# ECU_JUMPER.net
KiCad netlist of a schematic drawn in EAGLE
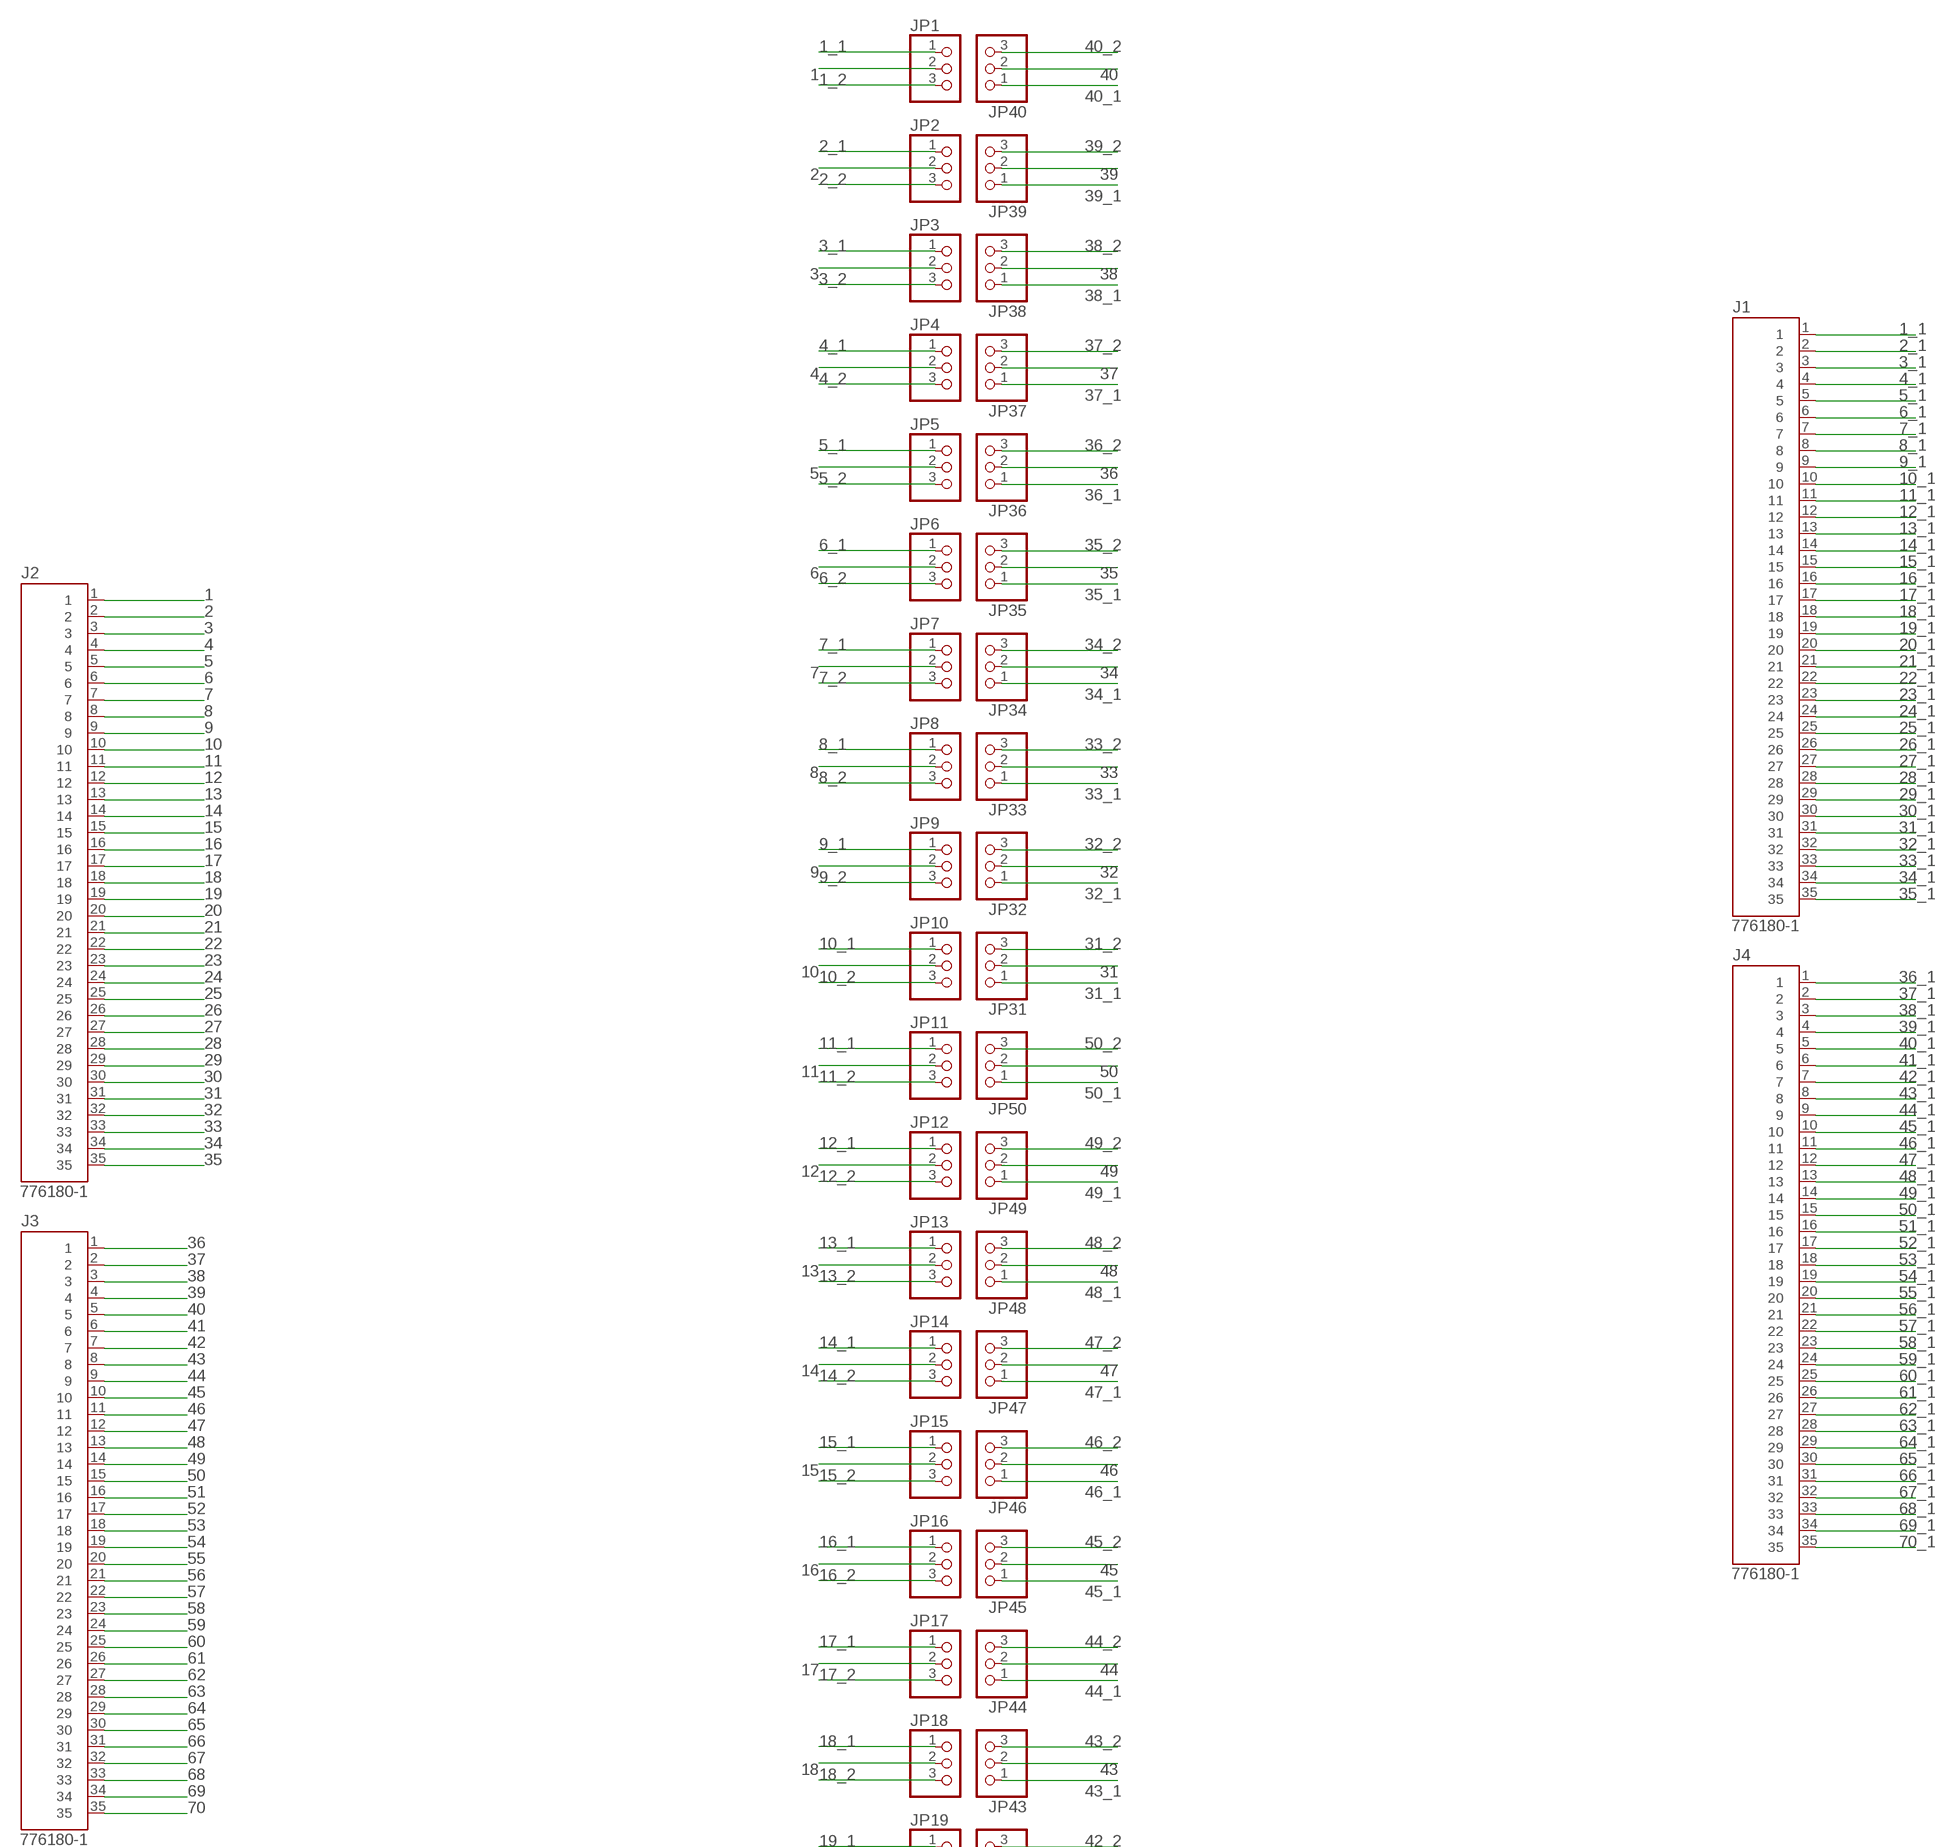
[diagram p0: schematic, sheet 1, part 1 of 2]
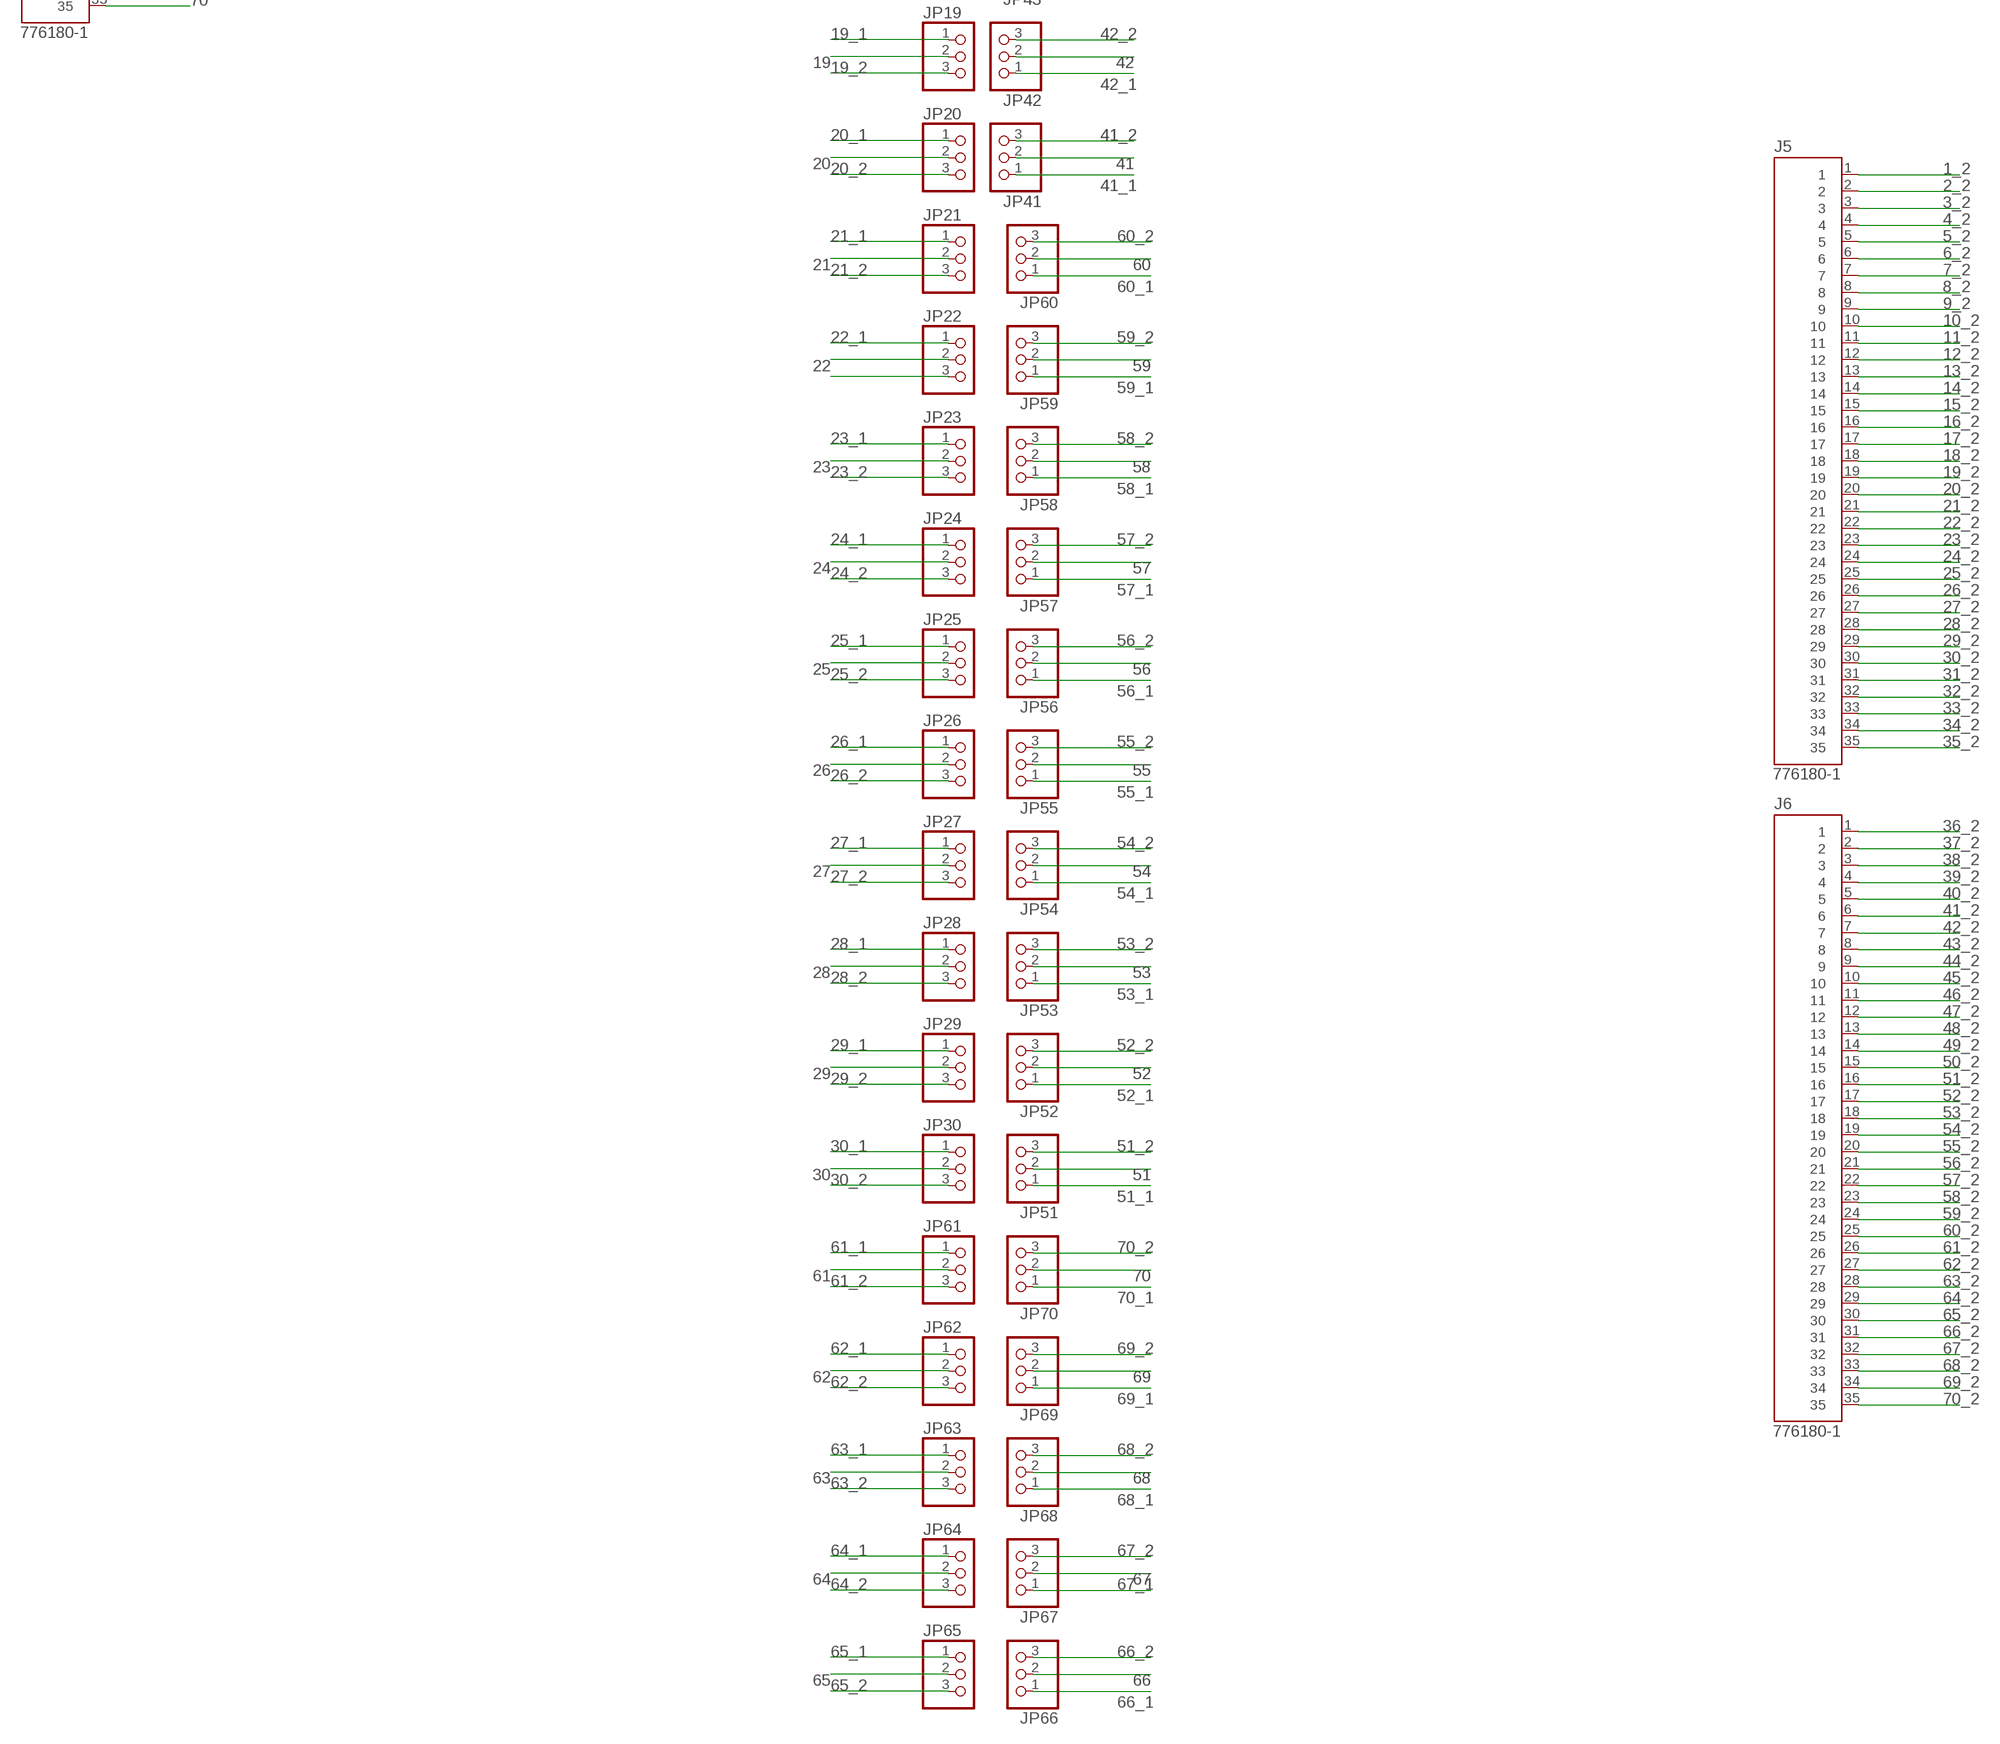
[diagram p1: schematic, sheet 1, part 2 of 2]

(export (version "E")
  (design (tool "Eeschema 10.0.6"))
  (components
    (comp (ref "J1")
      (value "776180-1")
      (footprint "eagle-import:TE_776180-1")
      (fields (field (name "MANUFACTURER") "TE CONNECTIVITY"))
      (libsource (lib "eagle-import") (part "776180-1"))
    )
    (comp (ref "J2")
      (value "776180-1")
      (footprint "eagle-import:TE_776180-1")
      (fields (field (name "MANUFACTURER") "TE CONNECTIVITY"))
      (libsource (lib "eagle-import") (part "776180-1"))
    )
    (comp (ref "J3")
      (value "776180-1")
      (footprint "eagle-import:TE_776180-1")
      (fields (field (name "MANUFACTURER") "TE CONNECTIVITY"))
      (libsource (lib "eagle-import") (part "776180-1"))
    )
    (comp (ref "J4")
      (value "776180-1")
      (footprint "eagle-import:TE_776180-1")
      (fields (field (name "MANUFACTURER") "TE CONNECTIVITY"))
      (libsource (lib "eagle-import") (part "776180-1"))
    )
    (comp (ref "J5")
      (value "776180-1")
      (footprint "eagle-import:TE_776180-1")
      (fields (field (name "MANUFACTURER") "TE CONNECTIVITY"))
      (libsource (lib "eagle-import") (part "776180-1"))
    )
    (comp (ref "J6")
      (value "776180-1")
      (footprint "eagle-import:TE_776180-1")
      (fields (field (name "MANUFACTURER") "TE CONNECTIVITY"))
      (libsource (lib "eagle-import") (part "776180-1"))
    )
    (comp (ref "JP1")
      (value "PINHD-1X3")
      (footprint "eagle-import:1X03")
      (libsource (lib "eagle-import") (part "PINHD-1X3"))
    )
    (comp (ref "JP2")
      (value "PINHD-1X3")
      (footprint "eagle-import:1X03")
      (libsource (lib "eagle-import") (part "PINHD-1X3"))
    )
    (comp (ref "JP3")
      (value "PINHD-1X3")
      (footprint "eagle-import:1X03")
      (libsource (lib "eagle-import") (part "PINHD-1X3"))
    )
    (comp (ref "JP4")
      (value "PINHD-1X3")
      (footprint "eagle-import:1X03")
      (libsource (lib "eagle-import") (part "PINHD-1X3"))
    )
    (comp (ref "JP5")
      (value "PINHD-1X3")
      (footprint "eagle-import:1X03")
      (libsource (lib "eagle-import") (part "PINHD-1X3"))
    )
    (comp (ref "JP6")
      (value "PINHD-1X3")
      (footprint "eagle-import:1X03")
      (libsource (lib "eagle-import") (part "PINHD-1X3"))
    )
    (comp (ref "JP7")
      (value "PINHD-1X3")
      (footprint "eagle-import:1X03")
      (libsource (lib "eagle-import") (part "PINHD-1X3"))
    )
    (comp (ref "JP8")
      (value "PINHD-1X3")
      (footprint "eagle-import:1X03")
      (libsource (lib "eagle-import") (part "PINHD-1X3"))
    )
    (comp (ref "JP9")
      (value "PINHD-1X3")
      (footprint "eagle-import:1X03")
      (libsource (lib "eagle-import") (part "PINHD-1X3"))
    )
    (comp (ref "JP10")
      (value "PINHD-1X3")
      (footprint "eagle-import:1X03")
      (libsource (lib "eagle-import") (part "PINHD-1X3"))
    )
    (comp (ref "JP11")
      (value "PINHD-1X3")
      (footprint "eagle-import:1X03")
      (libsource (lib "eagle-import") (part "PINHD-1X3"))
    )
    (comp (ref "JP12")
      (value "PINHD-1X3")
      (footprint "eagle-import:1X03")
      (libsource (lib "eagle-import") (part "PINHD-1X3"))
    )
    (comp (ref "JP13")
      (value "PINHD-1X3")
      (footprint "eagle-import:1X03")
      (libsource (lib "eagle-import") (part "PINHD-1X3"))
    )
    (comp (ref "JP14")
      (value "PINHD-1X3")
      (footprint "eagle-import:1X03")
      (libsource (lib "eagle-import") (part "PINHD-1X3"))
    )
    (comp (ref "JP15")
      (value "PINHD-1X3")
      (footprint "eagle-import:1X03")
      (libsource (lib "eagle-import") (part "PINHD-1X3"))
    )
    (comp (ref "JP16")
      (value "PINHD-1X3")
      (footprint "eagle-import:1X03")
      (libsource (lib "eagle-import") (part "PINHD-1X3"))
    )
    (comp (ref "JP17")
      (value "PINHD-1X3")
      (footprint "eagle-import:1X03")
      (libsource (lib "eagle-import") (part "PINHD-1X3"))
    )
    (comp (ref "JP18")
      (value "PINHD-1X3")
      (footprint "eagle-import:1X03")
      (libsource (lib "eagle-import") (part "PINHD-1X3"))
    )
    (comp (ref "JP19")
      (value "PINHD-1X3")
      (footprint "eagle-import:1X03")
      (libsource (lib "eagle-import") (part "PINHD-1X3"))
    )
    (comp (ref "JP20")
      (value "PINHD-1X3")
      (footprint "eagle-import:1X03")
      (libsource (lib "eagle-import") (part "PINHD-1X3"))
    )
    (comp (ref "JP21")
      (value "PINHD-1X3")
      (footprint "eagle-import:1X03")
      (libsource (lib "eagle-import") (part "PINHD-1X3"))
    )
    (comp (ref "JP22")
      (value "PINHD-1X3")
      (footprint "eagle-import:1X03")
      (libsource (lib "eagle-import") (part "PINHD-1X3"))
    )
    (comp (ref "JP23")
      (value "PINHD-1X3")
      (footprint "eagle-import:1X03")
      (libsource (lib "eagle-import") (part "PINHD-1X3"))
    )
    (comp (ref "JP24")
      (value "PINHD-1X3")
      (footprint "eagle-import:1X03")
      (libsource (lib "eagle-import") (part "PINHD-1X3"))
    )
    (comp (ref "JP25")
      (value "PINHD-1X3")
      (footprint "eagle-import:1X03")
      (libsource (lib "eagle-import") (part "PINHD-1X3"))
    )
    (comp (ref "JP26")
      (value "PINHD-1X3")
      (footprint "eagle-import:1X03")
      (libsource (lib "eagle-import") (part "PINHD-1X3"))
    )
    (comp (ref "JP27")
      (value "PINHD-1X3")
      (footprint "eagle-import:1X03")
      (libsource (lib "eagle-import") (part "PINHD-1X3"))
    )
    (comp (ref "JP28")
      (value "PINHD-1X3")
      (footprint "eagle-import:1X03")
      (libsource (lib "eagle-import") (part "PINHD-1X3"))
    )
    (comp (ref "JP29")
      (value "PINHD-1X3")
      (footprint "eagle-import:1X03")
      (libsource (lib "eagle-import") (part "PINHD-1X3"))
    )
    (comp (ref "JP30")
      (value "PINHD-1X3")
      (footprint "eagle-import:1X03")
      (libsource (lib "eagle-import") (part "PINHD-1X3"))
    )
    (comp (ref "JP31")
      (value "PINHD-1X3")
      (footprint "eagle-import:1X03")
      (libsource (lib "eagle-import") (part "PINHD-1X3"))
    )
    (comp (ref "JP32")
      (value "PINHD-1X3")
      (footprint "eagle-import:1X03")
      (libsource (lib "eagle-import") (part "PINHD-1X3"))
    )
    (comp (ref "JP33")
      (value "PINHD-1X3")
      (footprint "eagle-import:1X03")
      (libsource (lib "eagle-import") (part "PINHD-1X3"))
    )
    (comp (ref "JP34")
      (value "PINHD-1X3")
      (footprint "eagle-import:1X03")
      (libsource (lib "eagle-import") (part "PINHD-1X3"))
    )
    (comp (ref "JP35")
      (value "PINHD-1X3")
      (footprint "eagle-import:1X03")
      (libsource (lib "eagle-import") (part "PINHD-1X3"))
    )
    (comp (ref "JP36")
      (value "PINHD-1X3")
      (footprint "eagle-import:1X03")
      (libsource (lib "eagle-import") (part "PINHD-1X3"))
    )
    (comp (ref "JP37")
      (value "PINHD-1X3")
      (footprint "eagle-import:1X03")
      (libsource (lib "eagle-import") (part "PINHD-1X3"))
    )
    (comp (ref "JP38")
      (value "PINHD-1X3")
      (footprint "eagle-import:1X03")
      (libsource (lib "eagle-import") (part "PINHD-1X3"))
    )
    (comp (ref "JP39")
      (value "PINHD-1X3")
      (footprint "eagle-import:1X03")
      (libsource (lib "eagle-import") (part "PINHD-1X3"))
    )
    (comp (ref "JP40")
      (value "PINHD-1X3")
      (footprint "eagle-import:1X03")
      (libsource (lib "eagle-import") (part "PINHD-1X3"))
    )
    (comp (ref "JP41")
      (value "PINHD-1X3")
      (footprint "eagle-import:1X03")
      (libsource (lib "eagle-import") (part "PINHD-1X3"))
    )
    (comp (ref "JP42")
      (value "PINHD-1X3")
      (footprint "eagle-import:1X03")
      (libsource (lib "eagle-import") (part "PINHD-1X3"))
    )
    (comp (ref "JP43")
      (value "PINHD-1X3")
      (footprint "eagle-import:1X03")
      (libsource (lib "eagle-import") (part "PINHD-1X3"))
    )
    (comp (ref "JP44")
      (value "PINHD-1X3")
      (footprint "eagle-import:1X03")
      (libsource (lib "eagle-import") (part "PINHD-1X3"))
    )
    (comp (ref "JP45")
      (value "PINHD-1X3")
      (footprint "eagle-import:1X03")
      (libsource (lib "eagle-import") (part "PINHD-1X3"))
    )
    (comp (ref "JP46")
      (value "PINHD-1X3")
      (footprint "eagle-import:1X03")
      (libsource (lib "eagle-import") (part "PINHD-1X3"))
    )
    (comp (ref "JP47")
      (value "PINHD-1X3")
      (footprint "eagle-import:1X03")
      (libsource (lib "eagle-import") (part "PINHD-1X3"))
    )
    (comp (ref "JP48")
      (value "PINHD-1X3")
      (footprint "eagle-import:1X03")
      (libsource (lib "eagle-import") (part "PINHD-1X3"))
    )
    (comp (ref "JP49")
      (value "PINHD-1X3")
      (footprint "eagle-import:1X03")
      (libsource (lib "eagle-import") (part "PINHD-1X3"))
    )
    (comp (ref "JP50")
      (value "PINHD-1X3")
      (footprint "eagle-import:1X03")
      (libsource (lib "eagle-import") (part "PINHD-1X3"))
    )
    (comp (ref "JP51")
      (value "PINHD-1X3")
      (footprint "eagle-import:1X03")
      (libsource (lib "eagle-import") (part "PINHD-1X3"))
    )
    (comp (ref "JP52")
      (value "PINHD-1X3")
      (footprint "eagle-import:1X03")
      (libsource (lib "eagle-import") (part "PINHD-1X3"))
    )
    (comp (ref "JP53")
      (value "PINHD-1X3")
      (footprint "eagle-import:1X03")
      (libsource (lib "eagle-import") (part "PINHD-1X3"))
    )
    (comp (ref "JP54")
      (value "PINHD-1X3")
      (footprint "eagle-import:1X03")
      (libsource (lib "eagle-import") (part "PINHD-1X3"))
    )
    (comp (ref "JP55")
      (value "PINHD-1X3")
      (footprint "eagle-import:1X03")
      (libsource (lib "eagle-import") (part "PINHD-1X3"))
    )
    (comp (ref "JP56")
      (value "PINHD-1X3")
      (footprint "eagle-import:1X03")
      (libsource (lib "eagle-import") (part "PINHD-1X3"))
    )
    (comp (ref "JP57")
      (value "PINHD-1X3")
      (footprint "eagle-import:1X03")
      (libsource (lib "eagle-import") (part "PINHD-1X3"))
    )
    (comp (ref "JP58")
      (value "PINHD-1X3")
      (footprint "eagle-import:1X03")
      (libsource (lib "eagle-import") (part "PINHD-1X3"))
    )
    (comp (ref "JP59")
      (value "PINHD-1X3")
      (footprint "eagle-import:1X03")
      (libsource (lib "eagle-import") (part "PINHD-1X3"))
    )
    (comp (ref "JP60")
      (value "PINHD-1X3")
      (footprint "eagle-import:1X03")
      (libsource (lib "eagle-import") (part "PINHD-1X3"))
    )
    (comp (ref "JP61")
      (value "PINHD-1X3")
      (footprint "eagle-import:1X03")
      (libsource (lib "eagle-import") (part "PINHD-1X3"))
    )
    (comp (ref "JP62")
      (value "PINHD-1X3")
      (footprint "eagle-import:1X03")
      (libsource (lib "eagle-import") (part "PINHD-1X3"))
    )
    (comp (ref "JP63")
      (value "PINHD-1X3")
      (footprint "eagle-import:1X03")
      (libsource (lib "eagle-import") (part "PINHD-1X3"))
    )
    (comp (ref "JP64")
      (value "PINHD-1X3")
      (footprint "eagle-import:1X03")
      (libsource (lib "eagle-import") (part "PINHD-1X3"))
    )
    (comp (ref "JP65")
      (value "PINHD-1X3")
      (footprint "eagle-import:1X03")
      (libsource (lib "eagle-import") (part "PINHD-1X3"))
    )
    (comp (ref "JP66")
      (value "PINHD-1X3")
      (footprint "eagle-import:1X03")
      (libsource (lib "eagle-import") (part "PINHD-1X3"))
    )
    (comp (ref "JP67")
      (value "PINHD-1X3")
      (footprint "eagle-import:1X03")
      (libsource (lib "eagle-import") (part "PINHD-1X3"))
    )
    (comp (ref "JP68")
      (value "PINHD-1X3")
      (footprint "eagle-import:1X03")
      (libsource (lib "eagle-import") (part "PINHD-1X3"))
    )
    (comp (ref "JP69")
      (value "PINHD-1X3")
      (footprint "eagle-import:1X03")
      (libsource (lib "eagle-import") (part "PINHD-1X3"))
    )
    (comp (ref "JP70")
      (value "PINHD-1X3")
      (footprint "eagle-import:1X03")
      (libsource (lib "eagle-import") (part "PINHD-1X3"))
    )
  )
  (nets
    (net (code "1") (name "/1") (class "Default")
      (node (ref "J2") (pin "1") (pinfunction "1_1") (pintype "passive"))
      (node (ref "JP1") (pin "2") (pinfunction "2_2") (pintype "passive"))
    )
    (net (code "2") (name "/1_1") (class "Default")
      (node (ref "J1") (pin "1") (pinfunction "1_1") (pintype "passive"))
      (node (ref "JP1") (pin "1") (pinfunction "1_1") (pintype "passive"))
    )
    (net (code "3") (name "/1_2") (class "Default")
      (node (ref "J5") (pin "1") (pinfunction "1_1") (pintype "passive"))
      (node (ref "JP1") (pin "3") (pinfunction "3_3") (pintype "passive"))
    )
    (net (code "4") (name "/2") (class "Default")
      (node (ref "J2") (pin "2") (pinfunction "2_2") (pintype "passive"))
      (node (ref "JP2") (pin "2") (pinfunction "2_2") (pintype "passive"))
    )
    (net (code "5") (name "/2_1") (class "Default")
      (node (ref "J1") (pin "2") (pinfunction "2_2") (pintype "passive"))
      (node (ref "JP2") (pin "1") (pinfunction "1_1") (pintype "passive"))
    )
    (net (code "6") (name "/2_2") (class "Default")
      (node (ref "J5") (pin "2") (pinfunction "2_2") (pintype "passive"))
      (node (ref "JP2") (pin "3") (pinfunction "3_3") (pintype "passive"))
    )
    (net (code "7") (name "/3") (class "Default")
      (node (ref "J2") (pin "3") (pinfunction "3_3") (pintype "passive"))
      (node (ref "JP3") (pin "2") (pinfunction "2_2") (pintype "passive"))
    )
    (net (code "8") (name "/3_1") (class "Default")
      (node (ref "J1") (pin "3") (pinfunction "3_3") (pintype "passive"))
      (node (ref "JP3") (pin "1") (pinfunction "1_1") (pintype "passive"))
    )
    (net (code "9") (name "/3_2") (class "Default")
      (node (ref "J5") (pin "3") (pinfunction "3_3") (pintype "passive"))
      (node (ref "JP3") (pin "3") (pinfunction "3_3") (pintype "passive"))
    )
    (net (code "10") (name "/4") (class "Default")
      (node (ref "J2") (pin "4") (pinfunction "4_4") (pintype "passive"))
      (node (ref "JP4") (pin "2") (pinfunction "2_2") (pintype "passive"))
    )
    (net (code "11") (name "/4_1") (class "Default")
      (node (ref "J1") (pin "4") (pinfunction "4_4") (pintype "passive"))
      (node (ref "JP4") (pin "1") (pinfunction "1_1") (pintype "passive"))
    )
    (net (code "12") (name "/4_2") (class "Default")
      (node (ref "J5") (pin "4") (pinfunction "4_4") (pintype "passive"))
      (node (ref "JP4") (pin "3") (pinfunction "3_3") (pintype "passive"))
    )
    (net (code "13") (name "/5") (class "Default")
      (node (ref "J2") (pin "5") (pinfunction "5_5") (pintype "passive"))
      (node (ref "JP5") (pin "2") (pinfunction "2_2") (pintype "passive"))
    )
    (net (code "14") (name "/5_1") (class "Default")
      (node (ref "J1") (pin "5") (pinfunction "5_5") (pintype "passive"))
      (node (ref "JP5") (pin "1") (pinfunction "1_1") (pintype "passive"))
    )
    (net (code "15") (name "/5_2") (class "Default")
      (node (ref "J5") (pin "5") (pinfunction "5_5") (pintype "passive"))
      (node (ref "JP5") (pin "3") (pinfunction "3_3") (pintype "passive"))
    )
    (net (code "16") (name "/6") (class "Default")
      (node (ref "J2") (pin "6") (pinfunction "6_6") (pintype "passive"))
      (node (ref "JP6") (pin "2") (pinfunction "2_2") (pintype "passive"))
    )
    (net (code "17") (name "/6_1") (class "Default")
      (node (ref "J1") (pin "6") (pinfunction "6_6") (pintype "passive"))
      (node (ref "JP6") (pin "1") (pinfunction "1_1") (pintype "passive"))
    )
    (net (code "18") (name "/6_2") (class "Default")
      (node (ref "J5") (pin "6") (pinfunction "6_6") (pintype "passive"))
      (node (ref "JP6") (pin "3") (pinfunction "3_3") (pintype "passive"))
    )
    (net (code "19") (name "/7") (class "Default")
      (node (ref "J2") (pin "7") (pinfunction "7_7") (pintype "passive"))
      (node (ref "JP7") (pin "2") (pinfunction "2_2") (pintype "passive"))
    )
    (net (code "20") (name "/7_1") (class "Default")
      (node (ref "J1") (pin "7") (pinfunction "7_7") (pintype "passive"))
      (node (ref "JP7") (pin "1") (pinfunction "1_1") (pintype "passive"))
    )
    (net (code "21") (name "/7_2") (class "Default")
      (node (ref "J5") (pin "7") (pinfunction "7_7") (pintype "passive"))
      (node (ref "JP7") (pin "3") (pinfunction "3_3") (pintype "passive"))
    )
    (net (code "22") (name "/8") (class "Default")
      (node (ref "J2") (pin "8") (pinfunction "8_8") (pintype "passive"))
      (node (ref "JP8") (pin "2") (pinfunction "2_2") (pintype "passive"))
    )
    (net (code "23") (name "/8_1") (class "Default")
      (node (ref "J1") (pin "8") (pinfunction "8_8") (pintype "passive"))
      (node (ref "JP8") (pin "1") (pinfunction "1_1") (pintype "passive"))
    )
    (net (code "24") (name "/8_2") (class "Default")
      (node (ref "J5") (pin "8") (pinfunction "8_8") (pintype "passive"))
      (node (ref "JP8") (pin "3") (pinfunction "3_3") (pintype "passive"))
    )
    (net (code "25") (name "/9") (class "Default")
      (node (ref "J2") (pin "9") (pinfunction "9_9") (pintype "passive"))
      (node (ref "JP9") (pin "2") (pinfunction "2_2") (pintype "passive"))
    )
    (net (code "26") (name "/9_1") (class "Default")
      (node (ref "J1") (pin "9") (pinfunction "9_9") (pintype "passive"))
      (node (ref "JP9") (pin "1") (pinfunction "1_1") (pintype "passive"))
    )
    (net (code "27") (name "/9_2") (class "Default")
      (node (ref "J5") (pin "9") (pinfunction "9_9") (pintype "passive"))
      (node (ref "JP9") (pin "3") (pinfunction "3_3") (pintype "passive"))
    )
    (net (code "28") (name "/10") (class "Default")
      (node (ref "J2") (pin "10") (pinfunction "10_10") (pintype "passive"))
      (node (ref "JP10") (pin "2") (pinfunction "2_2") (pintype "passive"))
    )
    (net (code "29") (name "/10_1") (class "Default")
      (node (ref "J1") (pin "10") (pinfunction "10_10") (pintype "passive"))
      (node (ref "JP10") (pin "1") (pinfunction "1_1") (pintype "passive"))
    )
    (net (code "30") (name "/10_2") (class "Default")
      (node (ref "J5") (pin "10") (pinfunction "10_10") (pintype "passive"))
      (node (ref "JP10") (pin "3") (pinfunction "3_3") (pintype "passive"))
    )
    (net (code "31") (name "/11") (class "Default")
      (node (ref "J2") (pin "11") (pinfunction "11_11") (pintype "passive"))
      (node (ref "JP11") (pin "2") (pinfunction "2_2") (pintype "passive"))
    )
    (net (code "32") (name "/11_1") (class "Default")
      (node (ref "J1") (pin "11") (pinfunction "11_11") (pintype "passive"))
      (node (ref "JP11") (pin "1") (pinfunction "1_1") (pintype "passive"))
    )
    (net (code "33") (name "/11_2") (class "Default")
      (node (ref "J5") (pin "11") (pinfunction "11_11") (pintype "passive"))
      (node (ref "JP11") (pin "3") (pinfunction "3_3") (pintype "passive"))
    )
    (net (code "34") (name "/12") (class "Default")
      (node (ref "J2") (pin "12") (pinfunction "12_12") (pintype "passive"))
      (node (ref "JP12") (pin "2") (pinfunction "2_2") (pintype "passive"))
    )
    (net (code "35") (name "/12_1") (class "Default")
      (node (ref "J1") (pin "12") (pinfunction "12_12") (pintype "passive"))
      (node (ref "JP12") (pin "1") (pinfunction "1_1") (pintype "passive"))
    )
    (net (code "36") (name "/12_2") (class "Default")
      (node (ref "J5") (pin "12") (pinfunction "12_12") (pintype "passive"))
      (node (ref "JP12") (pin "3") (pinfunction "3_3") (pintype "passive"))
    )
    (net (code "37") (name "/13") (class "Default")
      (node (ref "J2") (pin "13") (pinfunction "13_13") (pintype "passive"))
      (node (ref "JP13") (pin "2") (pinfunction "2_2") (pintype "passive"))
    )
    (net (code "38") (name "/13_1") (class "Default")
      (node (ref "J1") (pin "13") (pinfunction "13_13") (pintype "passive"))
      (node (ref "JP13") (pin "1") (pinfunction "1_1") (pintype "passive"))
    )
    (net (code "39") (name "/13_2") (class "Default")
      (node (ref "J5") (pin "13") (pinfunction "13_13") (pintype "passive"))
      (node (ref "JP13") (pin "3") (pinfunction "3_3") (pintype "passive"))
    )
    (net (code "40") (name "/14") (class "Default")
      (node (ref "J2") (pin "14") (pinfunction "14_14") (pintype "passive"))
      (node (ref "JP14") (pin "2") (pinfunction "2_2") (pintype "passive"))
    )
    (net (code "41") (name "/14_1") (class "Default")
      (node (ref "J1") (pin "14") (pinfunction "14_14") (pintype "passive"))
      (node (ref "JP14") (pin "1") (pinfunction "1_1") (pintype "passive"))
    )
    (net (code "42") (name "/14_2") (class "Default")
      (node (ref "J5") (pin "14") (pinfunction "14_14") (pintype "passive"))
      (node (ref "JP14") (pin "3") (pinfunction "3_3") (pintype "passive"))
    )
    (net (code "43") (name "/15") (class "Default")
      (node (ref "J2") (pin "15") (pinfunction "15_15") (pintype "passive"))
      (node (ref "JP15") (pin "2") (pinfunction "2_2") (pintype "passive"))
    )
    (net (code "44") (name "/15_1") (class "Default")
      (node (ref "J1") (pin "15") (pinfunction "15_15") (pintype "passive"))
      (node (ref "JP15") (pin "1") (pinfunction "1_1") (pintype "passive"))
    )
    (net (code "45") (name "/15_2") (class "Default")
      (node (ref "J5") (pin "15") (pinfunction "15_15") (pintype "passive"))
      (node (ref "JP15") (pin "3") (pinfunction "3_3") (pintype "passive"))
    )
    (net (code "46") (name "/16") (class "Default")
      (node (ref "J2") (pin "16") (pinfunction "16_16") (pintype "passive"))
      (node (ref "JP16") (pin "2") (pinfunction "2_2") (pintype "passive"))
    )
    (net (code "47") (name "/16_1") (class "Default")
      (node (ref "J1") (pin "16") (pinfunction "16_16") (pintype "passive"))
      (node (ref "JP16") (pin "1") (pinfunction "1_1") (pintype "passive"))
    )
    (net (code "48") (name "/16_2") (class "Default")
      (node (ref "J5") (pin "16") (pinfunction "16_16") (pintype "passive"))
      (node (ref "JP16") (pin "3") (pinfunction "3_3") (pintype "passive"))
    )
    (net (code "49") (name "/17") (class "Default")
      (node (ref "J2") (pin "17") (pinfunction "17_17") (pintype "passive"))
      (node (ref "JP17") (pin "2") (pinfunction "2_2") (pintype "passive"))
    )
    (net (code "50") (name "/17_1") (class "Default")
      (node (ref "J1") (pin "17") (pinfunction "17_17") (pintype "passive"))
      (node (ref "JP17") (pin "1") (pinfunction "1_1") (pintype "passive"))
    )
    (net (code "51") (name "/17_2") (class "Default")
      (node (ref "J5") (pin "17") (pinfunction "17_17") (pintype "passive"))
      (node (ref "JP17") (pin "3") (pinfunction "3_3") (pintype "passive"))
    )
    (net (code "52") (name "/18") (class "Default")
      (node (ref "J2") (pin "18") (pinfunction "18_18") (pintype "passive"))
      (node (ref "JP18") (pin "2") (pinfunction "2_2") (pintype "passive"))
    )
    (net (code "53") (name "/18_1") (class "Default")
      (node (ref "J1") (pin "18") (pinfunction "18_18") (pintype "passive"))
      (node (ref "JP18") (pin "1") (pinfunction "1_1") (pintype "passive"))
    )
    (net (code "54") (name "/18_2") (class "Default")
      (node (ref "J5") (pin "18") (pinfunction "18_18") (pintype "passive"))
      (node (ref "JP18") (pin "3") (pinfunction "3_3") (pintype "passive"))
    )
    (net (code "55") (name "/19") (class "Default")
      (node (ref "J2") (pin "19") (pinfunction "19_19") (pintype "passive"))
      (node (ref "JP19") (pin "2") (pinfunction "2_2") (pintype "passive"))
    )
    (net (code "56") (name "/19_1") (class "Default")
      (node (ref "J1") (pin "19") (pinfunction "19_19") (pintype "passive"))
      (node (ref "JP19") (pin "1") (pinfunction "1_1") (pintype "passive"))
    )
    (net (code "57") (name "/19_2") (class "Default")
      (node (ref "J5") (pin "19") (pinfunction "19_19") (pintype "passive"))
      (node (ref "JP19") (pin "3") (pinfunction "3_3") (pintype "passive"))
    )
    (net (code "58") (name "/20") (class "Default")
      (node (ref "J2") (pin "20") (pinfunction "20_20") (pintype "passive"))
      (node (ref "JP20") (pin "2") (pinfunction "2_2") (pintype "passive"))
    )
    (net (code "59") (name "/20_1") (class "Default")
      (node (ref "J1") (pin "20") (pinfunction "20_20") (pintype "passive"))
      (node (ref "JP20") (pin "1") (pinfunction "1_1") (pintype "passive"))
    )
    (net (code "60") (name "/20_2") (class "Default")
      (node (ref "J5") (pin "20") (pinfunction "20_20") (pintype "passive"))
      (node (ref "JP20") (pin "3") (pinfunction "3_3") (pintype "passive"))
    )
    (net (code "61") (name "/21") (class "Default")
      (node (ref "J2") (pin "21") (pinfunction "21_21") (pintype "passive"))
      (node (ref "JP21") (pin "2") (pinfunction "2_2") (pintype "passive"))
    )
    (net (code "62") (name "/21_1") (class "Default")
      (node (ref "J1") (pin "21") (pinfunction "21_21") (pintype "passive"))
      (node (ref "JP21") (pin "1") (pinfunction "1_1") (pintype "passive"))
    )
    (net (code "63") (name "/21_2") (class "Default")
      (node (ref "J5") (pin "21") (pinfunction "21_21") (pintype "passive"))
      (node (ref "JP21") (pin "3") (pinfunction "3_3") (pintype "passive"))
    )
    (net (code "64") (name "/22") (class "Default")
      (node (ref "J2") (pin "22") (pinfunction "22_22") (pintype "passive"))
      (node (ref "JP22") (pin "2") (pinfunction "2_2") (pintype "passive"))
    )
    (net (code "65") (name "/22_1") (class "Default")
      (node (ref "J1") (pin "22") (pinfunction "22_22") (pintype "passive"))
      (node (ref "JP22") (pin "1") (pinfunction "1_1") (pintype "passive"))
    )
    (net (code "66") (name "/22_2") (class "Default")
      (node (ref "J5") (pin "22") (pinfunction "22_22") (pintype "passive"))
    )
    (net (code "67") (name "/23") (class "Default")
      (node (ref "J2") (pin "23") (pinfunction "23_23") (pintype "passive"))
      (node (ref "JP23") (pin "2") (pinfunction "2_2") (pintype "passive"))
    )
    (net (code "68") (name "/23_1") (class "Default")
      (node (ref "J1") (pin "23") (pinfunction "23_23") (pintype "passive"))
      (node (ref "JP23") (pin "1") (pinfunction "1_1") (pintype "passive"))
    )
    (net (code "69") (name "/23_2") (class "Default")
      (node (ref "J5") (pin "23") (pinfunction "23_23") (pintype "passive"))
      (node (ref "JP23") (pin "3") (pinfunction "3_3") (pintype "passive"))
    )
    (net (code "70") (name "/24") (class "Default")
      (node (ref "J2") (pin "24") (pinfunction "24_24") (pintype "passive"))
      (node (ref "JP24") (pin "2") (pinfunction "2_2") (pintype "passive"))
    )
    (net (code "71") (name "/24_1") (class "Default")
      (node (ref "J1") (pin "24") (pinfunction "24_24") (pintype "passive"))
      (node (ref "JP24") (pin "1") (pinfunction "1_1") (pintype "passive"))
    )
    (net (code "72") (name "/24_2") (class "Default")
      (node (ref "J5") (pin "24") (pinfunction "24_24") (pintype "passive"))
      (node (ref "JP24") (pin "3") (pinfunction "3_3") (pintype "passive"))
    )
    (net (code "73") (name "/25") (class "Default")
      (node (ref "J2") (pin "25") (pinfunction "25_25") (pintype "passive"))
      (node (ref "JP25") (pin "2") (pinfunction "2_2") (pintype "passive"))
    )
    (net (code "74") (name "/25_1") (class "Default")
      (node (ref "J1") (pin "25") (pinfunction "25_25") (pintype "passive"))
      (node (ref "JP25") (pin "1") (pinfunction "1_1") (pintype "passive"))
    )
    (net (code "75") (name "/25_2") (class "Default")
      (node (ref "J5") (pin "25") (pinfunction "25_25") (pintype "passive"))
      (node (ref "JP25") (pin "3") (pinfunction "3_3") (pintype "passive"))
    )
    (net (code "76") (name "/26") (class "Default")
      (node (ref "J2") (pin "26") (pinfunction "26_26") (pintype "passive"))
      (node (ref "JP26") (pin "2") (pinfunction "2_2") (pintype "passive"))
    )
    (net (code "77") (name "/26_1") (class "Default")
      (node (ref "J1") (pin "26") (pinfunction "26_26") (pintype "passive"))
      (node (ref "JP26") (pin "1") (pinfunction "1_1") (pintype "passive"))
    )
    (net (code "78") (name "/26_2") (class "Default")
      (node (ref "J5") (pin "26") (pinfunction "26_26") (pintype "passive"))
      (node (ref "JP26") (pin "3") (pinfunction "3_3") (pintype "passive"))
    )
    (net (code "79") (name "/27") (class "Default")
      (node (ref "J2") (pin "27") (pinfunction "27_27") (pintype "passive"))
      (node (ref "JP27") (pin "2") (pinfunction "2_2") (pintype "passive"))
    )
    (net (code "80") (name "/27_1") (class "Default")
      (node (ref "J1") (pin "27") (pinfunction "27_27") (pintype "passive"))
      (node (ref "JP27") (pin "1") (pinfunction "1_1") (pintype "passive"))
    )
    (net (code "81") (name "/27_2") (class "Default")
      (node (ref "J5") (pin "27") (pinfunction "27_27") (pintype "passive"))
      (node (ref "JP27") (pin "3") (pinfunction "3_3") (pintype "passive"))
    )
    (net (code "82") (name "/28") (class "Default")
      (node (ref "J2") (pin "28") (pinfunction "28_28") (pintype "passive"))
      (node (ref "JP28") (pin "2") (pinfunction "2_2") (pintype "passive"))
    )
    (net (code "83") (name "/28_1") (class "Default")
      (node (ref "J1") (pin "28") (pinfunction "28_28") (pintype "passive"))
      (node (ref "JP28") (pin "1") (pinfunction "1_1") (pintype "passive"))
    )
    (net (code "84") (name "/28_2") (class "Default")
      (node (ref "J5") (pin "28") (pinfunction "28_28") (pintype "passive"))
      (node (ref "JP28") (pin "3") (pinfunction "3_3") (pintype "passive"))
    )
    (net (code "85") (name "/29") (class "Default")
      (node (ref "J2") (pin "29") (pinfunction "29_29") (pintype "passive"))
      (node (ref "JP29") (pin "2") (pinfunction "2_2") (pintype "passive"))
    )
    (net (code "86") (name "/29_1") (class "Default")
      (node (ref "J1") (pin "29") (pinfunction "29_29") (pintype "passive"))
      (node (ref "JP29") (pin "1") (pinfunction "1_1") (pintype "passive"))
    )
    (net (code "87") (name "/29_2") (class "Default")
      (node (ref "J5") (pin "29") (pinfunction "29_29") (pintype "passive"))
      (node (ref "JP29") (pin "3") (pinfunction "3_3") (pintype "passive"))
    )
    (net (code "88") (name "/30") (class "Default")
      (node (ref "J2") (pin "30") (pinfunction "30_30") (pintype "passive"))
      (node (ref "JP30") (pin "2") (pinfunction "2_2") (pintype "passive"))
    )
    (net (code "89") (name "/30_1") (class "Default")
      (node (ref "J1") (pin "30") (pinfunction "30_30") (pintype "passive"))
      (node (ref "JP30") (pin "1") (pinfunction "1_1") (pintype "passive"))
    )
    (net (code "90") (name "/30_2") (class "Default")
      (node (ref "J5") (pin "30") (pinfunction "30_30") (pintype "passive"))
      (node (ref "JP30") (pin "3") (pinfunction "3_3") (pintype "passive"))
    )
    (net (code "91") (name "/31") (class "Default")
      (node (ref "J2") (pin "31") (pinfunction "31_31") (pintype "passive"))
      (node (ref "JP31") (pin "2") (pinfunction "2_2") (pintype "passive"))
    )
    (net (code "92") (name "/31_1") (class "Default")
      (node (ref "J1") (pin "31") (pinfunction "31_31") (pintype "passive"))
      (node (ref "JP31") (pin "1") (pinfunction "1_1") (pintype "passive"))
    )
    (net (code "93") (name "/31_2") (class "Default")
      (node (ref "J5") (pin "31") (pinfunction "31_31") (pintype "passive"))
      (node (ref "JP31") (pin "3") (pinfunction "3_3") (pintype "passive"))
    )
    (net (code "94") (name "/32") (class "Default")
      (node (ref "J2") (pin "32") (pinfunction "32_32") (pintype "passive"))
      (node (ref "JP32") (pin "2") (pinfunction "2_2") (pintype "passive"))
    )
    (net (code "95") (name "/32_1") (class "Default")
      (node (ref "J1") (pin "32") (pinfunction "32_32") (pintype "passive"))
      (node (ref "JP32") (pin "1") (pinfunction "1_1") (pintype "passive"))
    )
    (net (code "96") (name "/32_2") (class "Default")
      (node (ref "J5") (pin "32") (pinfunction "32_32") (pintype "passive"))
      (node (ref "JP32") (pin "3") (pinfunction "3_3") (pintype "passive"))
    )
    (net (code "97") (name "/33") (class "Default")
      (node (ref "J2") (pin "33") (pinfunction "33_33") (pintype "passive"))
      (node (ref "JP33") (pin "2") (pinfunction "2_2") (pintype "passive"))
    )
    (net (code "98") (name "/33_1") (class "Default")
      (node (ref "J1") (pin "33") (pinfunction "33_33") (pintype "passive"))
      (node (ref "JP33") (pin "1") (pinfunction "1_1") (pintype "passive"))
    )
    (net (code "99") (name "/33_2") (class "Default")
      (node (ref "J5") (pin "33") (pinfunction "33_33") (pintype "passive"))
      (node (ref "JP33") (pin "3") (pinfunction "3_3") (pintype "passive"))
    )
    (net (code "100") (name "/34") (class "Default")
      (node (ref "J2") (pin "34") (pinfunction "34_34") (pintype "passive"))
      (node (ref "JP34") (pin "2") (pinfunction "2_2") (pintype "passive"))
    )
    (net (code "101") (name "/34_1") (class "Default")
      (node (ref "J1") (pin "34") (pinfunction "34_34") (pintype "passive"))
      (node (ref "JP34") (pin "1") (pinfunction "1_1") (pintype "passive"))
    )
    (net (code "102") (name "/34_2") (class "Default")
      (node (ref "J5") (pin "34") (pinfunction "34_34") (pintype "passive"))
      (node (ref "JP34") (pin "3") (pinfunction "3_3") (pintype "passive"))
    )
    (net (code "103") (name "/35") (class "Default")
      (node (ref "J2") (pin "35") (pinfunction "35_35") (pintype "passive"))
      (node (ref "JP35") (pin "2") (pinfunction "2_2") (pintype "passive"))
    )
    (net (code "104") (name "/35_1") (class "Default")
      (node (ref "J1") (pin "35") (pinfunction "35_35") (pintype "passive"))
      (node (ref "JP35") (pin "1") (pinfunction "1_1") (pintype "passive"))
    )
    (net (code "105") (name "/35_2") (class "Default")
      (node (ref "J5") (pin "35") (pinfunction "35_35") (pintype "passive"))
      (node (ref "JP35") (pin "3") (pinfunction "3_3") (pintype "passive"))
    )
    (net (code "106") (name "/36") (class "Default")
      (node (ref "J3") (pin "1") (pinfunction "1_1") (pintype "passive"))
      (node (ref "JP36") (pin "2") (pinfunction "2_2") (pintype "passive"))
    )
    (net (code "107") (name "/36_1") (class "Default")
      (node (ref "J4") (pin "1") (pinfunction "1_1") (pintype "passive"))
      (node (ref "JP36") (pin "1") (pinfunction "1_1") (pintype "passive"))
    )
    (net (code "108") (name "/36_2") (class "Default")
      (node (ref "J6") (pin "1") (pinfunction "1_1") (pintype "passive"))
      (node (ref "JP36") (pin "3") (pinfunction "3_3") (pintype "passive"))
    )
    (net (code "109") (name "/37") (class "Default")
      (node (ref "J3") (pin "2") (pinfunction "2_2") (pintype "passive"))
      (node (ref "JP37") (pin "2") (pinfunction "2_2") (pintype "passive"))
    )
    (net (code "110") (name "/37_1") (class "Default")
      (node (ref "J4") (pin "2") (pinfunction "2_2") (pintype "passive"))
      (node (ref "JP37") (pin "1") (pinfunction "1_1") (pintype "passive"))
    )
    (net (code "111") (name "/37_2") (class "Default")
      (node (ref "J6") (pin "2") (pinfunction "2_2") (pintype "passive"))
      (node (ref "JP37") (pin "3") (pinfunction "3_3") (pintype "passive"))
    )
    (net (code "112") (name "/38") (class "Default")
      (node (ref "J3") (pin "3") (pinfunction "3_3") (pintype "passive"))
      (node (ref "JP38") (pin "2") (pinfunction "2_2") (pintype "passive"))
    )
    (net (code "113") (name "/38_1") (class "Default")
      (node (ref "J4") (pin "3") (pinfunction "3_3") (pintype "passive"))
      (node (ref "JP38") (pin "1") (pinfunction "1_1") (pintype "passive"))
    )
    (net (code "114") (name "/38_2") (class "Default")
      (node (ref "J6") (pin "3") (pinfunction "3_3") (pintype "passive"))
      (node (ref "JP38") (pin "3") (pinfunction "3_3") (pintype "passive"))
    )
    (net (code "115") (name "/39") (class "Default")
      (node (ref "J3") (pin "4") (pinfunction "4_4") (pintype "passive"))
      (node (ref "JP39") (pin "2") (pinfunction "2_2") (pintype "passive"))
    )
    (net (code "116") (name "/39_1") (class "Default")
      (node (ref "J4") (pin "4") (pinfunction "4_4") (pintype "passive"))
      (node (ref "JP39") (pin "1") (pinfunction "1_1") (pintype "passive"))
    )
    (net (code "117") (name "/39_2") (class "Default")
      (node (ref "J6") (pin "4") (pinfunction "4_4") (pintype "passive"))
      (node (ref "JP39") (pin "3") (pinfunction "3_3") (pintype "passive"))
    )
    (net (code "118") (name "/40") (class "Default")
      (node (ref "J3") (pin "5") (pinfunction "5_5") (pintype "passive"))
      (node (ref "JP40") (pin "2") (pinfunction "2_2") (pintype "passive"))
    )
    (net (code "119") (name "/40_1") (class "Default")
      (node (ref "J4") (pin "5") (pinfunction "5_5") (pintype "passive"))
      (node (ref "JP40") (pin "1") (pinfunction "1_1") (pintype "passive"))
    )
    (net (code "120") (name "/40_2") (class "Default")
      (node (ref "J6") (pin "5") (pinfunction "5_5") (pintype "passive"))
      (node (ref "JP40") (pin "3") (pinfunction "3_3") (pintype "passive"))
    )
    (net (code "121") (name "/41") (class "Default")
      (node (ref "J3") (pin "6") (pinfunction "6_6") (pintype "passive"))
      (node (ref "JP41") (pin "2") (pinfunction "2_2") (pintype "passive"))
    )
    (net (code "122") (name "/41_1") (class "Default")
      (node (ref "J4") (pin "6") (pinfunction "6_6") (pintype "passive"))
      (node (ref "JP41") (pin "1") (pinfunction "1_1") (pintype "passive"))
    )
    (net (code "123") (name "/41_2") (class "Default")
      (node (ref "J6") (pin "6") (pinfunction "6_6") (pintype "passive"))
      (node (ref "JP41") (pin "3") (pinfunction "3_3") (pintype "passive"))
    )
    (net (code "124") (name "/42") (class "Default")
      (node (ref "J3") (pin "7") (pinfunction "7_7") (pintype "passive"))
      (node (ref "JP42") (pin "2") (pinfunction "2_2") (pintype "passive"))
    )
    (net (code "125") (name "/42_1") (class "Default")
      (node (ref "J4") (pin "7") (pinfunction "7_7") (pintype "passive"))
      (node (ref "JP42") (pin "1") (pinfunction "1_1") (pintype "passive"))
    )
    (net (code "126") (name "/42_2") (class "Default")
      (node (ref "J6") (pin "7") (pinfunction "7_7") (pintype "passive"))
      (node (ref "JP42") (pin "3") (pinfunction "3_3") (pintype "passive"))
    )
    (net (code "127") (name "/43") (class "Default")
      (node (ref "J3") (pin "8") (pinfunction "8_8") (pintype "passive"))
      (node (ref "JP43") (pin "2") (pinfunction "2_2") (pintype "passive"))
    )
    (net (code "128") (name "/43_1") (class "Default")
      (node (ref "J4") (pin "8") (pinfunction "8_8") (pintype "passive"))
      (node (ref "JP43") (pin "1") (pinfunction "1_1") (pintype "passive"))
    )
    (net (code "129") (name "/43_2") (class "Default")
      (node (ref "J6") (pin "8") (pinfunction "8_8") (pintype "passive"))
      (node (ref "JP43") (pin "3") (pinfunction "3_3") (pintype "passive"))
    )
    (net (code "130") (name "/44") (class "Default")
      (node (ref "J3") (pin "9") (pinfunction "9_9") (pintype "passive"))
      (node (ref "JP44") (pin "2") (pinfunction "2_2") (pintype "passive"))
    )
    (net (code "131") (name "/44_1") (class "Default")
      (node (ref "J4") (pin "9") (pinfunction "9_9") (pintype "passive"))
      (node (ref "JP44") (pin "1") (pinfunction "1_1") (pintype "passive"))
    )
    (net (code "132") (name "/44_2") (class "Default")
      (node (ref "J6") (pin "9") (pinfunction "9_9") (pintype "passive"))
      (node (ref "JP44") (pin "3") (pinfunction "3_3") (pintype "passive"))
    )
    (net (code "133") (name "/45") (class "Default")
      (node (ref "J3") (pin "10") (pinfunction "10_10") (pintype "passive"))
      (node (ref "JP45") (pin "2") (pinfunction "2_2") (pintype "passive"))
    )
    (net (code "134") (name "/45_1") (class "Default")
      (node (ref "J4") (pin "10") (pinfunction "10_10") (pintype "passive"))
      (node (ref "JP45") (pin "1") (pinfunction "1_1") (pintype "passive"))
    )
    (net (code "135") (name "/45_2") (class "Default")
      (node (ref "J6") (pin "10") (pinfunction "10_10") (pintype "passive"))
      (node (ref "JP45") (pin "3") (pinfunction "3_3") (pintype "passive"))
    )
    (net (code "136") (name "/46") (class "Default")
      (node (ref "J3") (pin "11") (pinfunction "11_11") (pintype "passive"))
      (node (ref "JP46") (pin "2") (pinfunction "2_2") (pintype "passive"))
    )
    (net (code "137") (name "/46_1") (class "Default")
      (node (ref "J4") (pin "11") (pinfunction "11_11") (pintype "passive"))
      (node (ref "JP46") (pin "1") (pinfunction "1_1") (pintype "passive"))
    )
    (net (code "138") (name "/46_2") (class "Default")
      (node (ref "J6") (pin "11") (pinfunction "11_11") (pintype "passive"))
      (node (ref "JP46") (pin "3") (pinfunction "3_3") (pintype "passive"))
    )
    (net (code "139") (name "/47") (class "Default")
      (node (ref "J3") (pin "12") (pinfunction "12_12") (pintype "passive"))
      (node (ref "JP47") (pin "2") (pinfunction "2_2") (pintype "passive"))
    )
    (net (code "140") (name "/47_1") (class "Default")
      (node (ref "J4") (pin "12") (pinfunction "12_12") (pintype "passive"))
      (node (ref "JP47") (pin "1") (pinfunction "1_1") (pintype "passive"))
    )
    (net (code "141") (name "/47_2") (class "Default")
      (node (ref "J6") (pin "12") (pinfunction "12_12") (pintype "passive"))
      (node (ref "JP47") (pin "3") (pinfunction "3_3") (pintype "passive"))
    )
    (net (code "142") (name "/48") (class "Default")
      (node (ref "J3") (pin "13") (pinfunction "13_13") (pintype "passive"))
      (node (ref "JP48") (pin "2") (pinfunction "2_2") (pintype "passive"))
    )
    (net (code "143") (name "/48_1") (class "Default")
      (node (ref "J4") (pin "13") (pinfunction "13_13") (pintype "passive"))
      (node (ref "JP48") (pin "1") (pinfunction "1_1") (pintype "passive"))
    )
    (net (code "144") (name "/48_2") (class "Default")
      (node (ref "J6") (pin "13") (pinfunction "13_13") (pintype "passive"))
      (node (ref "JP48") (pin "3") (pinfunction "3_3") (pintype "passive"))
    )
    (net (code "145") (name "/49") (class "Default")
      (node (ref "J3") (pin "14") (pinfunction "14_14") (pintype "passive"))
      (node (ref "JP49") (pin "2") (pinfunction "2_2") (pintype "passive"))
    )
    (net (code "146") (name "/49_1") (class "Default")
      (node (ref "J4") (pin "14") (pinfunction "14_14") (pintype "passive"))
      (node (ref "JP49") (pin "1") (pinfunction "1_1") (pintype "passive"))
    )
    (net (code "147") (name "/49_2") (class "Default")
      (node (ref "J6") (pin "14") (pinfunction "14_14") (pintype "passive"))
      (node (ref "JP49") (pin "3") (pinfunction "3_3") (pintype "passive"))
    )
    (net (code "148") (name "/50") (class "Default")
      (node (ref "J3") (pin "15") (pinfunction "15_15") (pintype "passive"))
      (node (ref "JP50") (pin "2") (pinfunction "2_2") (pintype "passive"))
    )
    (net (code "149") (name "/50_1") (class "Default")
      (node (ref "J4") (pin "15") (pinfunction "15_15") (pintype "passive"))
      (node (ref "JP50") (pin "1") (pinfunction "1_1") (pintype "passive"))
    )
    (net (code "150") (name "/50_2") (class "Default")
      (node (ref "J6") (pin "15") (pinfunction "15_15") (pintype "passive"))
      (node (ref "JP50") (pin "3") (pinfunction "3_3") (pintype "passive"))
    )
    (net (code "151") (name "/51") (class "Default")
      (node (ref "J3") (pin "16") (pinfunction "16_16") (pintype "passive"))
      (node (ref "JP51") (pin "2") (pinfunction "2_2") (pintype "passive"))
    )
    (net (code "152") (name "/51_1") (class "Default")
      (node (ref "J4") (pin "16") (pinfunction "16_16") (pintype "passive"))
      (node (ref "JP51") (pin "1") (pinfunction "1_1") (pintype "passive"))
    )
    (net (code "153") (name "/51_2") (class "Default")
      (node (ref "J6") (pin "16") (pinfunction "16_16") (pintype "passive"))
      (node (ref "JP51") (pin "3") (pinfunction "3_3") (pintype "passive"))
    )
    (net (code "154") (name "/52") (class "Default")
      (node (ref "J3") (pin "17") (pinfunction "17_17") (pintype "passive"))
      (node (ref "JP52") (pin "2") (pinfunction "2_2") (pintype "passive"))
    )
    (net (code "155") (name "/52_1") (class "Default")
      (node (ref "J4") (pin "17") (pinfunction "17_17") (pintype "passive"))
      (node (ref "JP52") (pin "1") (pinfunction "1_1") (pintype "passive"))
    )
    (net (code "156") (name "/52_2") (class "Default")
      (node (ref "J6") (pin "17") (pinfunction "17_17") (pintype "passive"))
      (node (ref "JP52") (pin "3") (pinfunction "3_3") (pintype "passive"))
    )
    (net (code "157") (name "/53") (class "Default")
      (node (ref "J3") (pin "18") (pinfunction "18_18") (pintype "passive"))
      (node (ref "JP53") (pin "2") (pinfunction "2_2") (pintype "passive"))
    )
    (net (code "158") (name "/53_1") (class "Default")
      (node (ref "J4") (pin "18") (pinfunction "18_18") (pintype "passive"))
      (node (ref "JP53") (pin "1") (pinfunction "1_1") (pintype "passive"))
    )
    (net (code "159") (name "/53_2") (class "Default")
      (node (ref "J6") (pin "18") (pinfunction "18_18") (pintype "passive"))
      (node (ref "JP53") (pin "3") (pinfunction "3_3") (pintype "passive"))
    )
    (net (code "160") (name "/54") (class "Default")
      (node (ref "J3") (pin "19") (pinfunction "19_19") (pintype "passive"))
      (node (ref "JP54") (pin "2") (pinfunction "2_2") (pintype "passive"))
    )
    (net (code "161") (name "/54_1") (class "Default")
      (node (ref "J4") (pin "19") (pinfunction "19_19") (pintype "passive"))
      (node (ref "JP54") (pin "1") (pinfunction "1_1") (pintype "passive"))
    )
    (net (code "162") (name "/54_2") (class "Default")
      (node (ref "J6") (pin "19") (pinfunction "19_19") (pintype "passive"))
      (node (ref "JP54") (pin "3") (pinfunction "3_3") (pintype "passive"))
    )
    (net (code "163") (name "/55") (class "Default")
      (node (ref "J3") (pin "20") (pinfunction "20_20") (pintype "passive"))
      (node (ref "JP55") (pin "2") (pinfunction "2_2") (pintype "passive"))
    )
    (net (code "164") (name "/55_1") (class "Default")
      (node (ref "J4") (pin "20") (pinfunction "20_20") (pintype "passive"))
      (node (ref "JP55") (pin "1") (pinfunction "1_1") (pintype "passive"))
    )
    (net (code "165") (name "/55_2") (class "Default")
      (node (ref "J6") (pin "20") (pinfunction "20_20") (pintype "passive"))
      (node (ref "JP55") (pin "3") (pinfunction "3_3") (pintype "passive"))
    )
    (net (code "166") (name "/56") (class "Default")
      (node (ref "J3") (pin "21") (pinfunction "21_21") (pintype "passive"))
      (node (ref "JP56") (pin "2") (pinfunction "2_2") (pintype "passive"))
    )
    (net (code "167") (name "/56_1") (class "Default")
      (node (ref "J4") (pin "21") (pinfunction "21_21") (pintype "passive"))
      (node (ref "JP56") (pin "1") (pinfunction "1_1") (pintype "passive"))
    )
    (net (code "168") (name "/56_2") (class "Default")
      (node (ref "J6") (pin "21") (pinfunction "21_21") (pintype "passive"))
      (node (ref "JP56") (pin "3") (pinfunction "3_3") (pintype "passive"))
    )
    (net (code "169") (name "/57") (class "Default")
      (node (ref "J3") (pin "22") (pinfunction "22_22") (pintype "passive"))
      (node (ref "JP57") (pin "2") (pinfunction "2_2") (pintype "passive"))
    )
    (net (code "170") (name "/57_1") (class "Default")
      (node (ref "J4") (pin "22") (pinfunction "22_22") (pintype "passive"))
      (node (ref "JP57") (pin "1") (pinfunction "1_1") (pintype "passive"))
    )
    (net (code "171") (name "/57_2") (class "Default")
      (node (ref "J6") (pin "22") (pinfunction "22_22") (pintype "passive"))
      (node (ref "JP57") (pin "3") (pinfunction "3_3") (pintype "passive"))
    )
    (net (code "172") (name "/58") (class "Default")
      (node (ref "J3") (pin "23") (pinfunction "23_23") (pintype "passive"))
      (node (ref "JP58") (pin "2") (pinfunction "2_2") (pintype "passive"))
    )
    (net (code "173") (name "/58_1") (class "Default")
      (node (ref "J4") (pin "23") (pinfunction "23_23") (pintype "passive"))
      (node (ref "JP58") (pin "1") (pinfunction "1_1") (pintype "passive"))
    )
    (net (code "174") (name "/58_2") (class "Default")
      (node (ref "J6") (pin "23") (pinfunction "23_23") (pintype "passive"))
      (node (ref "JP58") (pin "3") (pinfunction "3_3") (pintype "passive"))
    )
    (net (code "175") (name "/59") (class "Default")
      (node (ref "J3") (pin "24") (pinfunction "24_24") (pintype "passive"))
      (node (ref "JP59") (pin "2") (pinfunction "2_2") (pintype "passive"))
    )
    (net (code "176") (name "/59_1") (class "Default")
      (node (ref "J4") (pin "24") (pinfunction "24_24") (pintype "passive"))
      (node (ref "JP59") (pin "1") (pinfunction "1_1") (pintype "passive"))
    )
    (net (code "177") (name "/59_2") (class "Default")
      (node (ref "J6") (pin "24") (pinfunction "24_24") (pintype "passive"))
      (node (ref "JP59") (pin "3") (pinfunction "3_3") (pintype "passive"))
    )
    (net (code "178") (name "/60") (class "Default")
      (node (ref "J3") (pin "25") (pinfunction "25_25") (pintype "passive"))
      (node (ref "JP60") (pin "2") (pinfunction "2_2") (pintype "passive"))
    )
    (net (code "179") (name "/60_1") (class "Default")
      (node (ref "J4") (pin "25") (pinfunction "25_25") (pintype "passive"))
      (node (ref "JP60") (pin "1") (pinfunction "1_1") (pintype "passive"))
    )
    (net (code "180") (name "/60_2") (class "Default")
      (node (ref "J6") (pin "25") (pinfunction "25_25") (pintype "passive"))
      (node (ref "JP60") (pin "3") (pinfunction "3_3") (pintype "passive"))
    )
    (net (code "181") (name "/61") (class "Default")
      (node (ref "J3") (pin "26") (pinfunction "26_26") (pintype "passive"))
      (node (ref "JP61") (pin "2") (pinfunction "2_2") (pintype "passive"))
    )
    (net (code "182") (name "/61_1") (class "Default")
      (node (ref "J4") (pin "26") (pinfunction "26_26") (pintype "passive"))
      (node (ref "JP61") (pin "1") (pinfunction "1_1") (pintype "passive"))
    )
    (net (code "183") (name "/61_2") (class "Default")
      (node (ref "J6") (pin "26") (pinfunction "26_26") (pintype "passive"))
      (node (ref "JP61") (pin "3") (pinfunction "3_3") (pintype "passive"))
    )
    (net (code "184") (name "/62") (class "Default")
      (node (ref "J3") (pin "27") (pinfunction "27_27") (pintype "passive"))
      (node (ref "JP62") (pin "2") (pinfunction "2_2") (pintype "passive"))
    )
    (net (code "185") (name "/62_1") (class "Default")
      (node (ref "J4") (pin "27") (pinfunction "27_27") (pintype "passive"))
      (node (ref "JP62") (pin "1") (pinfunction "1_1") (pintype "passive"))
    )
    (net (code "186") (name "/62_2") (class "Default")
      (node (ref "J6") (pin "27") (pinfunction "27_27") (pintype "passive"))
      (node (ref "JP62") (pin "3") (pinfunction "3_3") (pintype "passive"))
    )
    (net (code "187") (name "/63") (class "Default")
      (node (ref "J3") (pin "28") (pinfunction "28_28") (pintype "passive"))
      (node (ref "JP63") (pin "2") (pinfunction "2_2") (pintype "passive"))
    )
    (net (code "188") (name "/63_1") (class "Default")
      (node (ref "J4") (pin "28") (pinfunction "28_28") (pintype "passive"))
      (node (ref "JP63") (pin "1") (pinfunction "1_1") (pintype "passive"))
    )
    (net (code "189") (name "/63_2") (class "Default")
      (node (ref "J6") (pin "28") (pinfunction "28_28") (pintype "passive"))
      (node (ref "JP63") (pin "3") (pinfunction "3_3") (pintype "passive"))
    )
    (net (code "190") (name "/64") (class "Default")
      (node (ref "J3") (pin "29") (pinfunction "29_29") (pintype "passive"))
      (node (ref "JP64") (pin "2") (pinfunction "2_2") (pintype "passive"))
    )
    (net (code "191") (name "/64_1") (class "Default")
      (node (ref "J4") (pin "29") (pinfunction "29_29") (pintype "passive"))
      (node (ref "JP64") (pin "1") (pinfunction "1_1") (pintype "passive"))
    )
    (net (code "192") (name "/64_2") (class "Default")
      (node (ref "J6") (pin "29") (pinfunction "29_29") (pintype "passive"))
      (node (ref "JP64") (pin "3") (pinfunction "3_3") (pintype "passive"))
    )
    (net (code "193") (name "/65") (class "Default")
      (node (ref "J3") (pin "30") (pinfunction "30_30") (pintype "passive"))
      (node (ref "JP65") (pin "2") (pinfunction "2_2") (pintype "passive"))
    )
    (net (code "194") (name "/65_1") (class "Default")
      (node (ref "J4") (pin "30") (pinfunction "30_30") (pintype "passive"))
      (node (ref "JP65") (pin "1") (pinfunction "1_1") (pintype "passive"))
    )
    (net (code "195") (name "/65_2") (class "Default")
      (node (ref "J6") (pin "30") (pinfunction "30_30") (pintype "passive"))
      (node (ref "JP65") (pin "3") (pinfunction "3_3") (pintype "passive"))
    )
    (net (code "196") (name "/66") (class "Default")
      (node (ref "J3") (pin "31") (pinfunction "31_31") (pintype "passive"))
      (node (ref "JP66") (pin "2") (pinfunction "2_2") (pintype "passive"))
    )
    (net (code "197") (name "/66_1") (class "Default")
      (node (ref "J4") (pin "31") (pinfunction "31_31") (pintype "passive"))
      (node (ref "JP66") (pin "1") (pinfunction "1_1") (pintype "passive"))
    )
    (net (code "198") (name "/66_2") (class "Default")
      (node (ref "J6") (pin "31") (pinfunction "31_31") (pintype "passive"))
      (node (ref "JP66") (pin "3") (pinfunction "3_3") (pintype "passive"))
    )
    (net (code "199") (name "/67") (class "Default")
      (node (ref "J3") (pin "32") (pinfunction "32_32") (pintype "passive"))
      (node (ref "JP67") (pin "2") (pinfunction "2_2") (pintype "passive"))
    )
    (net (code "200") (name "/67_1") (class "Default")
      (node (ref "J4") (pin "32") (pinfunction "32_32") (pintype "passive"))
      (node (ref "JP67") (pin "1") (pinfunction "1_1") (pintype "passive"))
    )
    (net (code "201") (name "/67_2") (class "Default")
      (node (ref "J6") (pin "32") (pinfunction "32_32") (pintype "passive"))
      (node (ref "JP67") (pin "3") (pinfunction "3_3") (pintype "passive"))
    )
    (net (code "202") (name "/68") (class "Default")
      (node (ref "J3") (pin "33") (pinfunction "33_33") (pintype "passive"))
      (node (ref "JP68") (pin "2") (pinfunction "2_2") (pintype "passive"))
    )
    (net (code "203") (name "/68_1") (class "Default")
      (node (ref "J4") (pin "33") (pinfunction "33_33") (pintype "passive"))
      (node (ref "JP68") (pin "1") (pinfunction "1_1") (pintype "passive"))
    )
    (net (code "204") (name "/68_2") (class "Default")
      (node (ref "J6") (pin "33") (pinfunction "33_33") (pintype "passive"))
      (node (ref "JP68") (pin "3") (pinfunction "3_3") (pintype "passive"))
    )
    (net (code "205") (name "/69") (class "Default")
      (node (ref "J3") (pin "34") (pinfunction "34_34") (pintype "passive"))
      (node (ref "JP69") (pin "2") (pinfunction "2_2") (pintype "passive"))
    )
    (net (code "206") (name "/69_1") (class "Default")
      (node (ref "J4") (pin "34") (pinfunction "34_34") (pintype "passive"))
      (node (ref "JP69") (pin "1") (pinfunction "1_1") (pintype "passive"))
    )
    (net (code "207") (name "/69_2") (class "Default")
      (node (ref "J6") (pin "34") (pinfunction "34_34") (pintype "passive"))
      (node (ref "JP69") (pin "3") (pinfunction "3_3") (pintype "passive"))
    )
    (net (code "208") (name "/70") (class "Default")
      (node (ref "J3") (pin "35") (pinfunction "35_35") (pintype "passive"))
      (node (ref "JP70") (pin "2") (pinfunction "2_2") (pintype "passive"))
    )
    (net (code "209") (name "/70_1") (class "Default")
      (node (ref "J4") (pin "35") (pinfunction "35_35") (pintype "passive"))
      (node (ref "JP70") (pin "1") (pinfunction "1_1") (pintype "passive"))
    )
    (net (code "210") (name "/70_2") (class "Default")
      (node (ref "J6") (pin "35") (pinfunction "35_35") (pintype "passive"))
      (node (ref "JP70") (pin "3") (pinfunction "3_3") (pintype "passive"))
    )
    (net (code "211") (name "unconnected-(JP22-Pad3)") (class "Default")
      (node (ref "JP22") (pin "3") (pinfunction "3_3") (pintype "passive"))
    )
  )
)
